# AD835.net
KiCad netlist of a schematic drawn in Altium Designer
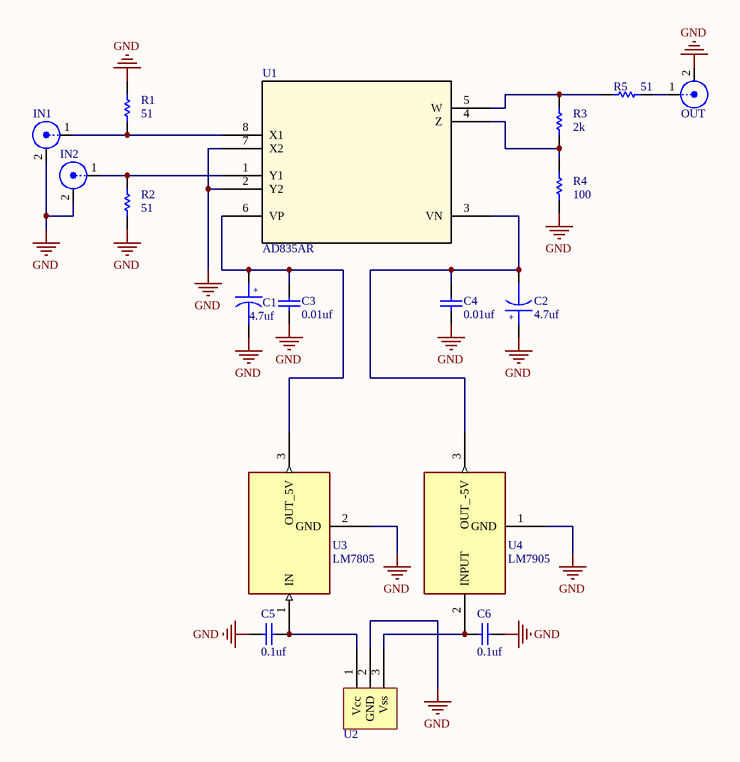
[diagram p0: AD835乘法器.SchDoc]

(export (version "E")
  (design (tool "Eeschema 10.0.6"))
  (components
    (comp (ref "C1") (value "4.7uf") (footprint "7343C-TYPE_D") (libsource (lib "钽电容") (part "Cap")))
    (comp (ref "C2") (value "4.7uf") (footprint "7343C-TYPE_D") (libsource (lib "钽电容") (part "Cap")))
    (comp (ref "C3")
      (value "0.01uF")
      (footprint "0805")
      (fields (field (name "值") "0.01uf"))
      (libsource (lib "电源") (part "Cap1"))
    )
    (comp (ref "C4")
      (value "Cap1")
      (footprint "0805")
      (fields (field (name "值") "0.01uf"))
      (libsource (lib "电源") (part "Cap1"))
    )
    (comp (ref "C5")
      (value "Cap1")
      (footprint "0805")
      (fields (field (name "值") "0.1uf"))
      (libsource (lib "电源") (part "Cap1"))
    )
    (comp (ref "C6")
      (value "Cap1")
      (footprint "0805")
      (fields (field (name "值") "0.1uf"))
      (libsource (lib "电源") (part "Cap1"))
    )
    (comp (ref "IN1") (value "SMA-2") (footprint "SMA-2") (libsource (lib "SMA") (part "SMA-2")))
    (comp (ref "IN2") (value "SMA-2") (footprint "SMA-2") (libsource (lib "SMA") (part "SMA-2")))
    (comp (ref "OUT") (value "SMA-2") (footprint "SMA-2") (libsource (lib "SMA") (part "SMA-2")))
    (comp (ref "R1")
      (value "RES")
      (footprint "0805")
      (fields (field (name "值") "51"))
      (libsource (lib "电源") (part "RES"))
    )
    (comp (ref "R2")
      (value "RES")
      (footprint "0805")
      (fields (field (name "值") "51"))
      (libsource (lib "电源") (part "RES"))
    )
    (comp (ref "R3")
      (value "RES")
      (footprint "0805")
      (fields (field (name "值") "2k"))
      (libsource (lib "电源") (part "RES"))
    )
    (comp (ref "R4")
      (value "RES")
      (footprint "0805")
      (fields (field (name "值") "100"))
      (libsource (lib "电源") (part "RES"))
    )
    (comp (ref "R5")
      (value "RES")
      (footprint "0805")
      (fields (field (name "值") "51"))
      (libsource (lib "电源") (part "RES"))
    )
    (comp (ref "U1")
      (value "AD835AR")
      (footprint "R_8")
      (description "Imported")
      (libsource (lib "AD835AR") (part "AD835AR"))
    )
    (comp (ref "U2") (value "XH2.54-3p") (footprint "XH2.54-3p") (libsource (lib "电源") (part "XH2.54-3p")))
    (comp (ref "U3") (value "LM7805") (footprint "TO-220") (libsource (lib "LM7805") (part "LM7805")))
    (comp (ref "U4") (value "LM7905") (footprint "TO-220") (libsource (lib "LM7905") (part "LM7905")))
  )
  (nets
    (net (code "1") (name "GND") (class "Default")
      (node (ref "C1") (pin "2") (pinfunction "2_2") (pintype "passive"))
      (node (ref "C2") (pin "1") (pinfunction "1_1") (pintype "passive"))
      (node (ref "C3") (pin "1") (pinfunction "1_1") (pintype "passive"))
      (node (ref "C4") (pin "1") (pinfunction "1_1") (pintype "passive"))
      (node (ref "C5") (pin "1") (pinfunction "1_1") (pintype "passive"))
      (node (ref "C6") (pin "1") (pinfunction "1_1") (pintype "passive"))
      (node (ref "IN1") (pin "2") (pinfunction "GND_2") (pintype "passive"))
      (node (ref "IN2") (pin "2") (pinfunction "GND_2") (pintype "passive"))
      (node (ref "OUT") (pin "2") (pinfunction "GND_2") (pintype "passive"))
      (node (ref "R1") (pin "2") (pinfunction "2_2") (pintype "passive"))
      (node (ref "R2") (pin "1") (pinfunction "1_1") (pintype "passive"))
      (node (ref "R4") (pin "1") (pinfunction "1_1") (pintype "passive"))
      (node (ref "U1") (pin "2") (pinfunction "Y2_2") (pintype "passive"))
      (node (ref "U1") (pin "7") (pinfunction "X2_7") (pintype "passive"))
      (node (ref "U2") (pin "2") (pinfunction "GND_2") (pintype "passive"))
      (node (ref "U3") (pin "2") (pinfunction "GND_2") (pintype "passive"))
      (node (ref "U4") (pin "1") (pinfunction "GND_1") (pintype "passive"))
    )
    (net (code "2") (name "Net-(IN1-Signal)") (class "Default")
      (node (ref "IN1") (pin "1") (pinfunction "Signal_1") (pintype "passive"))
      (node (ref "R1") (pin "1") (pinfunction "1_1") (pintype "passive"))
      (node (ref "U1") (pin "8") (pinfunction "X1_8") (pintype "passive"))
    )
    (net (code "3") (name "Net-(IN2-Signal)") (class "Default")
      (node (ref "IN2") (pin "1") (pinfunction "Signal_1") (pintype "passive"))
      (node (ref "R2") (pin "2") (pinfunction "2_2") (pintype "passive"))
      (node (ref "U1") (pin "1") (pinfunction "Y1_1") (pintype "passive"))
    )
    (net (code "4") (name "Net-(OUT-Signal)") (class "Default")
      (node (ref "OUT") (pin "1") (pinfunction "Signal_1") (pintype "passive"))
      (node (ref "R5") (pin "2") (pinfunction "2_2") (pintype "passive"))
    )
    (net (code "5") (name "Net-(U1-VN)") (class "Default")
      (node (ref "C2") (pin "2") (pinfunction "2_2") (pintype "passive"))
      (node (ref "C4") (pin "2") (pinfunction "2_2") (pintype "passive"))
      (node (ref "U1") (pin "3") (pinfunction "VN_3") (pintype "power_in"))
      (node (ref "U4") (pin "3") (pinfunction "OUT_-5V_3") (pintype "output"))
    )
    (net (code "6") (name "Net-(U1-VP)") (class "Default")
      (node (ref "C1") (pin "1") (pinfunction "1_1") (pintype "passive"))
      (node (ref "C3") (pin "2") (pinfunction "2_2") (pintype "passive"))
      (node (ref "U1") (pin "6") (pinfunction "VP_6") (pintype "power_in"))
      (node (ref "U3") (pin "3") (pinfunction "OUT_5V_3") (pintype "output"))
    )
    (net (code "7") (name "Net-(U1-W)") (class "Default")
      (node (ref "R3") (pin "2") (pinfunction "2_2") (pintype "passive"))
      (node (ref "R5") (pin "1") (pinfunction "1_1") (pintype "passive"))
      (node (ref "U1") (pin "5") (pinfunction "W_5") (pintype "passive"))
    )
    (net (code "8") (name "Net-(U1-Z)") (class "Default")
      (node (ref "R3") (pin "1") (pinfunction "1_1") (pintype "passive"))
      (node (ref "R4") (pin "2") (pinfunction "2_2") (pintype "passive"))
      (node (ref "U1") (pin "4") (pinfunction "Z_4") (pintype "passive"))
    )
    (net (code "9") (name "Net-(U2-Vcc)") (class "Default")
      (node (ref "C5") (pin "2") (pinfunction "2_2") (pintype "passive"))
      (node (ref "U2") (pin "1") (pinfunction "Vcc_1") (pintype "passive"))
      (node (ref "U3") (pin "1") (pinfunction "IN_1") (pintype "input"))
    )
    (net (code "10") (name "Net-(U2-Vss)") (class "Default")
      (node (ref "C6") (pin "2") (pinfunction "2_2") (pintype "passive"))
      (node (ref "U2") (pin "3") (pinfunction "Vss_3") (pintype "passive"))
      (node (ref "U4") (pin "2") (pinfunction "INPUT_2") (pintype "passive"))
    )
  )
)
